# DebuggerConnector.net
KiCad netlist of a schematic drawn in EAGLE
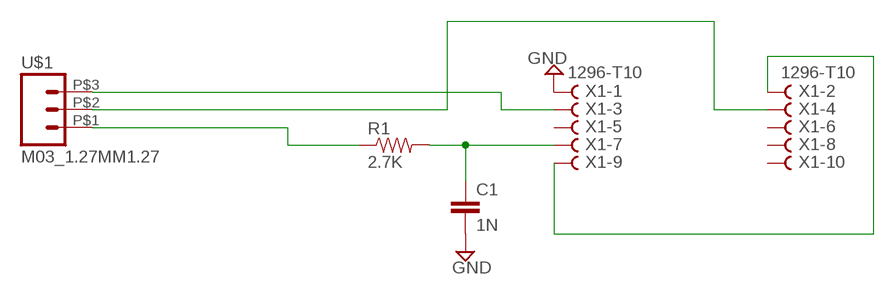
[diagram p0: schematic, sheet 1]

(export (version "E")
  (design (tool "Eeschema 10.0.6"))
  (components
    (comp (ref "C1")
      (value "1N")
      (footprint "eagle-import:0402-CAP")
      (libsource (lib "eagle-import") (part "CAP0402-CAP"))
    )
    (comp (ref "R1")
      (value "2.7K")
      (footprint "eagle-import:0402-RES")
      (libsource (lib "eagle-import") (part "RESISTOR0402-RES"))
    )
    (comp (ref "U$1")
      (value "M03_1.27MM1.27")
      (footprint "eagle-import:1X3_1.27MM")
      (libsource (lib "eagle-import") (part "M03_1.27MM1.27"))
    )
    (comp (ref "X1")
      (value "1296-T10")
      (footprint "eagle-import:1296-10")
      (libsource (lib "eagle-import") (part "1296-T10"))
    )
  )
  (nets
    (net (code "1") (name "GND") (class "Default")
      (node (ref "C1") (pin "2") (pinfunction "2_2") (pintype "passive"))
      (node (ref "X1") (pin "1") (pinfunction "B_1") (pintype "passive"))
    )
    (net (code "2") (name "Net-(U$1-1)") (class "Default")
      (node (ref "R1") (pin "1") (pinfunction "1_1") (pintype "passive"))
      (node (ref "U$1") (pin "P$1") (pinfunction "1_P$1") (pintype "passive"))
    )
    (net (code "3") (name "Net-(U$1-2)") (class "Default")
      (node (ref "U$1") (pin "P$2") (pinfunction "2_P$2") (pintype "passive"))
      (node (ref "X1") (pin "4") (pinfunction "B_4") (pintype "passive"))
    )
    (net (code "4") (name "Net-(U$1-3)") (class "Default")
      (node (ref "U$1") (pin "P$3") (pinfunction "3_P$3") (pintype "passive"))
      (node (ref "X1") (pin "3") (pinfunction "B_3") (pintype "passive"))
    )
    (net (code "5") (name "Net-(X1C-B)") (class "Default")
      (node (ref "X1") (pin "2") (pinfunction "B_2") (pintype "passive"))
      (node (ref "X1") (pin "9") (pinfunction "B_9") (pintype "passive"))
    )
    (net (code "6") (name "Net-(X1H-B)") (class "Default")
      (node (ref "C1") (pin "1") (pinfunction "1_1") (pintype "passive"))
      (node (ref "R1") (pin "2") (pinfunction "2_2") (pintype "passive"))
      (node (ref "X1") (pin "7") (pinfunction "B_7") (pintype "passive"))
    )
    (net (code "7") (name "unconnected-(X1B-B-Pad10)") (class "Default")
      (node (ref "X1") (pin "10") (pinfunction "B_10") (pintype "passive"))
    )
    (net (code "8") (name "unconnected-(X1F-B-Pad5)") (class "Default")
      (node (ref "X1") (pin "5") (pinfunction "B_5") (pintype "passive"))
    )
    (net (code "9") (name "unconnected-(X1G-B-Pad6)") (class "Default")
      (node (ref "X1") (pin "6") (pinfunction "B_6") (pintype "passive"))
    )
    (net (code "10") (name "unconnected-(X1I-B-Pad8)") (class "Default")
      (node (ref "X1") (pin "8") (pinfunction "B_8") (pintype "passive"))
    )
  )
)
